# Sheet1.net
KiCad netlist of a schematic drawn in Altium Designer
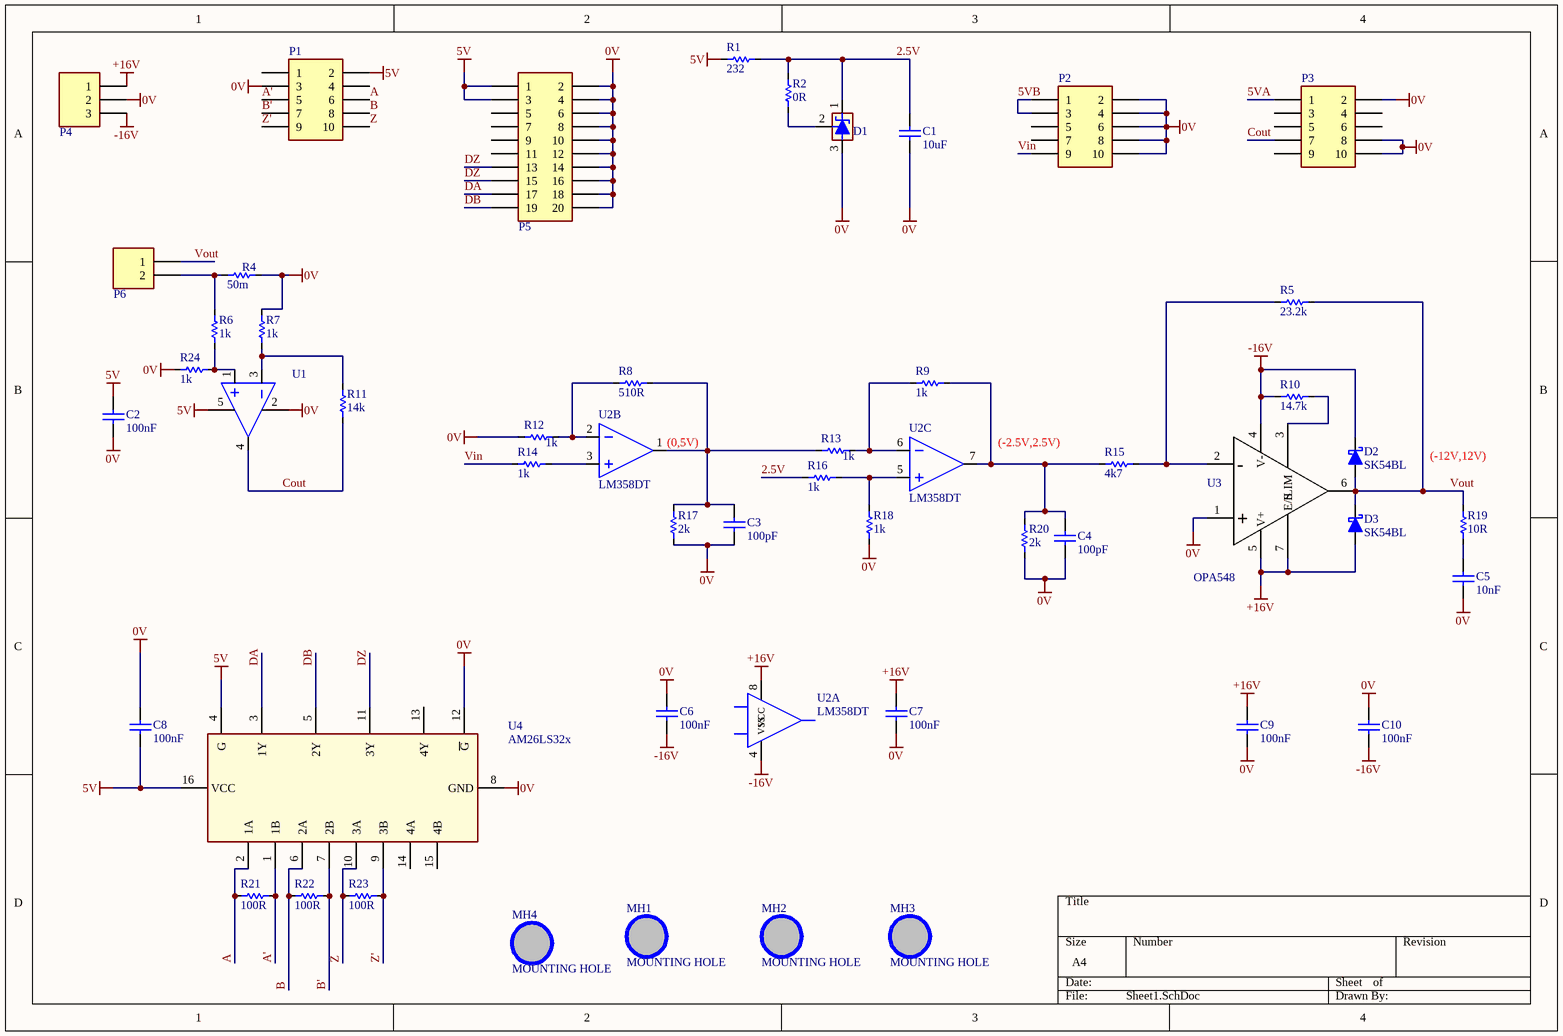
[diagram p0: Sheet1.SchDoc]

(export (version "E")
  (design (tool "Eeschema 10.0.6"))
  (components
    (comp (ref "C1")
      (value "10uF")
      (footprint "CC3216-1206L")
      (description "Capacitor")
      (libsource (lib "SchLibrary") (part "CAPACITOR NON-POL"))
    )
    (comp (ref "C2")
      (value "100nF")
      (footprint "CC3216-1206L")
      (description "Capacitor")
      (libsource (lib "SchLibrary") (part "CAPACITOR NON-POL"))
    )
    (comp (ref "C3")
      (value "100pF")
      (footprint "CC3216-1206L")
      (description "Capacitor")
      (libsource (lib "SchLibrary") (part "CAPACITOR NON-POL"))
    )
    (comp (ref "C4")
      (value "100pF")
      (footprint "CC3216-1206L")
      (description "Capacitor")
      (libsource (lib "SchLibrary") (part "CAPACITOR NON-POL"))
    )
    (comp (ref "C5")
      (value "10nF")
      (footprint "CC3216-1206L")
      (description "Capacitor")
      (libsource (lib "SchLibrary") (part "CAPACITOR NON-POL"))
    )
    (comp (ref "C6")
      (value "100nF")
      (footprint "CC3216-1206L")
      (description "Capacitor")
      (libsource (lib "SchLibrary") (part "CAPACITOR NON-POL"))
    )
    (comp (ref "C7")
      (value "100nF")
      (footprint "CC3216-1206L")
      (description "Capacitor")
      (libsource (lib "SchLibrary") (part "CAPACITOR NON-POL"))
    )
    (comp (ref "C8")
      (value "100nF")
      (footprint "CC3216-1206L")
      (description "Capacitor")
      (libsource (lib "SchLibrary") (part "CAPACITOR NON-POL"))
    )
    (comp (ref "C9")
      (value "100nF")
      (footprint "CC3216-1206L")
      (description "Capacitor")
      (libsource (lib "SchLibrary") (part "CAPACITOR NON-POL"))
    )
    (comp (ref "C10")
      (value "100nF")
      (footprint "CC3216-1206L")
      (description "Capacitor")
      (libsource (lib "SchLibrary") (part "CAPACITOR NON-POL"))
    )
    (comp (ref "D1")
      (value "TL431")
      (footprint "SOT95P230X110-3N")
      (description "REFERENCE DIODE PIN1:C, PIN2:REF, PIN3:A")
      (libsource (lib "SchLibrary") (part "TL431"))
    )
    (comp (ref "D2")
      (value "SK54BL")
      (footprint "PcbLibrary:SMB")
      (description "SINGLE SCHOTTKY DIODE\r\nCheck the suitability of the case with the pin number")
      (libsource (lib "SchLibrary") (part "DIODE SCHOTTKY"))
    )
    (comp (ref "D3")
      (value "SK54BL")
      (footprint "PcbLibrary:SMB")
      (description "SINGLE SCHOTTKY DIODE\r\nCheck the suitability of the case with the pin number")
      (libsource (lib "SchLibrary") (part "DIODE SCHOTTKY"))
    )
    (comp (ref "MH1")
      (value "MOUNTING HOLE")
      (footprint "PcbLibrary:MOUNTING HOLE ROUND NONPLATED 3MM PLASTIC")
      (libsource (lib "SchLibrary") (part "MOUNTING HOLE"))
    )
    (comp (ref "MH2")
      (value "MOUNTING HOLE")
      (footprint "PcbLibrary:MOUNTING HOLE ROUND NONPLATED 3MM PLASTIC")
      (libsource (lib "SchLibrary") (part "MOUNTING HOLE"))
    )
    (comp (ref "MH3")
      (value "MOUNTING HOLE")
      (footprint "PcbLibrary:MOUNTING HOLE ROUND NONPLATED 3MM PLASTIC")
      (libsource (lib "SchLibrary") (part "MOUNTING HOLE"))
    )
    (comp (ref "MH4")
      (value "MOUNTING HOLE")
      (footprint "PcbLibrary:MOUNTING HOLE ROUND NONPLATED 3MM PLASTIC")
      (libsource (lib "SchLibrary") (part "MOUNTING HOLE"))
    )
    (comp (ref "P1")
      (value "CONNECTOR, 2x5, 5P")
      (footprint "PcbLibrary:HDR_BOX_2X5_10P_2.54MM_180")
      (description "CONNECTOR, 2x5, 10P")
      (libsource (lib "SchLibrary") (part "CONNECTOR, 2x5, 10P"))
    )
    (comp (ref "P2")
      (value "CONNECTOR, 2x5, 5P")
      (footprint "PcbLibrary:HDR_FEMALE_2X5_10P_2.54MM_180")
      (description "CONNECTOR, 2x5, 10P")
      (libsource (lib "SchLibrary") (part "CONNECTOR, 2x5, 10P"))
    )
    (comp (ref "P3")
      (value "CONNECTOR, 2x5, 5P")
      (footprint "PcbLibrary:HDR_FEMALE_2X5_10P_2.54MM_180")
      (description "CONNECTOR, 2x5, 10P")
      (libsource (lib "SchLibrary") (part "CONNECTOR, 2x5, 10P"))
    )
    (comp (ref "P4")
      (value "CONNECTOR, 1x3, 3P")
      (footprint "PcbLibrary:2EDGR-5.08-03P")
      (libsource (lib "SchLibrary") (part "CONNECTOR, 1x3, 3P"))
    )
    (comp (ref "P5")
      (value "CONNECTOR, 2x10, 20P")
      (footprint "PcbLibrary:HDR_MALE_2X10_20P_2.54MM_180")
      (libsource (lib "SchLibrary") (part "CONNECTOR, 2x10, 20P"))
    )
    (comp (ref "P6")
      (value "CONNECTOR, 1x2, 2P")
      (footprint "PcbLibrary:DG128-5.0-02P-14")
      (libsource (lib "SchLibrary") (part "CONNECTOR, 1x2, 2P"))
    )
    (comp (ref "R1")
      (value "232")
      (footprint "CR3216-1206l")
      (description "Resistor")
      (libsource (lib "SchLibrary") (part "RESISTOR"))
    )
    (comp (ref "R2")
      (value "0R")
      (footprint "CR3216-1206l")
      (description "Resistor")
      (libsource (lib "SchLibrary") (part "RESISTOR"))
    )
    (comp (ref "R4")
      (value "50m")
      (footprint "CR3216-1206l")
      (description "Resistor")
      (libsource (lib "SchLibrary") (part "RESISTOR"))
    )
    (comp (ref "R5")
      (value "23.2k")
      (footprint "CR3216-1206l")
      (description "Resistor")
      (libsource (lib "SchLibrary") (part "RESISTOR"))
    )
    (comp (ref "R6")
      (value "1k")
      (footprint "CR3216-1206l")
      (description "Resistor")
      (libsource (lib "SchLibrary") (part "RESISTOR"))
    )
    (comp (ref "R7")
      (value "1k")
      (footprint "CR3216-1206l")
      (description "Resistor")
      (libsource (lib "SchLibrary") (part "RESISTOR"))
    )
    (comp (ref "R8")
      (value "510R")
      (footprint "CR3216-1206l")
      (description "Resistor")
      (libsource (lib "SchLibrary") (part "RESISTOR"))
    )
    (comp (ref "R9")
      (value "1k")
      (footprint "CR3216-1206l")
      (description "Resistor")
      (libsource (lib "SchLibrary") (part "RESISTOR"))
    )
    (comp (ref "R10")
      (value "14.7k")
      (footprint "CR3216-1206l")
      (description "Resistor")
      (libsource (lib "SchLibrary") (part "RESISTOR"))
    )
    (comp (ref "R11")
      (value "14k")
      (footprint "CR3216-1206l")
      (description "Resistor")
      (libsource (lib "SchLibrary") (part "RESISTOR"))
    )
    (comp (ref "R12")
      (value "1k")
      (footprint "CR3216-1206l")
      (description "Resistor")
      (libsource (lib "SchLibrary") (part "RESISTOR"))
    )
    (comp (ref "R13")
      (value "1k")
      (footprint "CR3216-1206l")
      (description "Resistor")
      (libsource (lib "SchLibrary") (part "RESISTOR"))
    )
    (comp (ref "R14")
      (value "1k")
      (footprint "CR3216-1206l")
      (description "Resistor")
      (libsource (lib "SchLibrary") (part "RESISTOR"))
    )
    (comp (ref "R15")
      (value "4k7")
      (footprint "CR3216-1206l")
      (description "Resistor")
      (libsource (lib "SchLibrary") (part "RESISTOR"))
    )
    (comp (ref "R16")
      (value "1k")
      (footprint "CR3216-1206l")
      (description "Resistor")
      (libsource (lib "SchLibrary") (part "RESISTOR"))
    )
    (comp (ref "R17")
      (value "2k")
      (footprint "CR3216-1206l")
      (description "Resistor")
      (libsource (lib "SchLibrary") (part "RESISTOR"))
    )
    (comp (ref "R18")
      (value "1k")
      (footprint "CR3216-1206l")
      (description "Resistor")
      (libsource (lib "SchLibrary") (part "RESISTOR"))
    )
    (comp (ref "R19")
      (value "10R")
      (footprint "CR3216-1206l")
      (description "Resistor")
      (libsource (lib "SchLibrary") (part "RESISTOR"))
    )
    (comp (ref "R20")
      (value "2k")
      (footprint "CR3216-1206l")
      (description "Resistor")
      (libsource (lib "SchLibrary") (part "RESISTOR"))
    )
    (comp (ref "R21")
      (value "100R")
      (footprint "CR3216-1206l")
      (description "Resistor")
      (libsource (lib "SchLibrary") (part "RESISTOR"))
    )
    (comp (ref "R22")
      (value "100R")
      (footprint "CR3216-1206l")
      (description "Resistor")
      (libsource (lib "SchLibrary") (part "RESISTOR"))
    )
    (comp (ref "R23")
      (value "100R")
      (footprint "CR3216-1206l")
      (description "Resistor")
      (libsource (lib "SchLibrary") (part "RESISTOR"))
    )
    (comp (ref "R24")
      (value "1k")
      (footprint "CR3216-1206l")
      (description "Resistor")
      (libsource (lib "SchLibrary") (part "RESISTOR"))
    )
    (comp (ref "U1")
      (value "LMV321")
      (footprint "LMV321IDBVTE4:SOT95P280X145-5N")
      (description "Single Opamp\r\nCheck the suitability of the case with the pin number")
      (libsource (lib "SchLibrary") (part "OPAMP1"))
    )
    (comp (ref "U2")
      (value "LM358DT")
      (footprint "SOIC127P600X175-8N")
      (description "Dual Opamp")
      (libsource (lib "SchLibrary") (part "OPAMP2"))
    )
    (comp (ref "U3")
      (value "OPA548")
      (footprint "TO127P1524X465-8N:TO127P1524X465-8N")
      (libsource (lib "SchLibrary") (part "OPA548"))
    )
    (comp (ref "U4")
      (value "AM26LS32x")
      (footprint "SOIC127P600X175-16N")
      (libsource (lib "SchLibrary") (part "AM26LS32x"))
    )
  )
  (nets
    (net (code "1") (name "+16V") (class "Default")
      (node (ref "C7") (pin "2") (pintype "passive"))
      (node (ref "C9") (pin "2") (pintype "passive"))
      (node (ref "D3") (pin "1") (pinfunction "1_1") (pintype "passive"))
      (node (ref "P4") (pin "1") (pinfunction "1_1") (pintype "passive"))
      (node (ref "U2") (pin "8") (pinfunction "VCC_8") (pintype "passive"))
      (node (ref "U3") (pin "5") (pinfunction "V+_5") (pintype "passive"))
      (node (ref "U3") (pin "7") (pinfunction "E/S_7") (pintype "passive"))
    )
    (net (code "2") (name "-16V") (class "Default")
      (node (ref "C10") (pin "1") (pintype "passive"))
      (node (ref "C6") (pin "1") (pintype "passive"))
      (node (ref "D2") (pin "2") (pinfunction "2_2") (pintype "passive"))
      (node (ref "P4") (pin "3") (pinfunction "3_3") (pintype "passive"))
      (node (ref "R10") (pin "2") (pinfunction "2_2") (pintype "passive"))
      (node (ref "U2") (pin "4") (pinfunction "VSS_4") (pintype "passive"))
      (node (ref "U3") (pin "4") (pinfunction "V-_4") (pintype "passive"))
    )
    (net (code "3") (name "/2.5V") (class "Default")
      (node (ref "C1") (pin "1") (pintype "passive"))
      (node (ref "D1") (pin "1") (pinfunction "C_1") (pintype "passive"))
      (node (ref "R1") (pin "1") (pinfunction "1_1") (pintype "passive"))
      (node (ref "R16") (pin "2") (pinfunction "2_2") (pintype "passive"))
      (node (ref "R2") (pin "2") (pinfunction "2_2") (pintype "passive"))
    )
    (net (code "4") (name "/5VA") (class "Default")
      (node (ref "P3") (pin "1") (pinfunction "1_1") (pintype "passive"))
    )
    (net (code "5") (name "/5VB") (class "Default")
      (node (ref "P2") (pin "1") (pinfunction "1_1") (pintype "passive"))
      (node (ref "P2") (pin "3") (pinfunction "3_3") (pintype "passive"))
    )
    (net (code "6") (name "/A") (class "Default")
      (node (ref "P1") (pin "6") (pinfunction "6_6") (pintype "passive"))
      (node (ref "R21") (pin "2") (pinfunction "2_2") (pintype "passive"))
      (node (ref "U4") (pin "2") (pinfunction "1A_2") (pintype "passive"))
    )
    (net (code "7") (name "/A'") (class "Default")
      (node (ref "P1") (pin "5") (pinfunction "5_5") (pintype "passive"))
      (node (ref "R21") (pin "1") (pinfunction "1_1") (pintype "passive"))
      (node (ref "U4") (pin "1") (pinfunction "1B_1") (pintype "passive"))
    )
    (net (code "8") (name "/B") (class "Default")
      (node (ref "P1") (pin "8") (pinfunction "8_8") (pintype "passive"))
      (node (ref "R22") (pin "2") (pinfunction "2_2") (pintype "passive"))
      (node (ref "U4") (pin "6") (pinfunction "2A_6") (pintype "passive"))
    )
    (net (code "9") (name "/B'") (class "Default")
      (node (ref "P1") (pin "7") (pinfunction "7_7") (pintype "passive"))
      (node (ref "R22") (pin "1") (pinfunction "1_1") (pintype "passive"))
      (node (ref "U4") (pin "7") (pinfunction "2B_7") (pintype "passive"))
    )
    (net (code "10") (name "/Cout") (class "Default")
      (node (ref "P3") (pin "7") (pinfunction "7_7") (pintype "passive"))
      (node (ref "R11") (pin "2") (pinfunction "2_2") (pintype "passive"))
      (node (ref "U1") (pin "4") (pinfunction "VSS_4") (pintype "passive"))
    )
    (net (code "11") (name "/DA") (class "Default")
      (node (ref "P5") (pin "17") (pinfunction "17_17") (pintype "passive"))
      (node (ref "U4") (pin "3") (pinfunction "1Y_3") (pintype "passive"))
    )
    (net (code "12") (name "/DB") (class "Default")
      (node (ref "P5") (pin "19") (pinfunction "19_19") (pintype "passive"))
      (node (ref "U4") (pin "5") (pinfunction "2Y_5") (pintype "passive"))
    )
    (net (code "13") (name "/DZ") (class "Default")
      (node (ref "P5") (pin "13") (pinfunction "13_13") (pintype "passive"))
      (node (ref "P5") (pin "15") (pinfunction "15_15") (pintype "passive"))
      (node (ref "U4") (pin "11") (pinfunction "3Y_11") (pintype "passive"))
    )
    (net (code "14") (name "/Vin") (class "Default")
      (node (ref "P2") (pin "9") (pinfunction "9_9") (pintype "passive"))
      (node (ref "R14") (pin "2") (pinfunction "2_2") (pintype "passive"))
    )
    (net (code "15") (name "/Vout") (class "Default")
      (node (ref "D2") (pin "1") (pinfunction "1_1") (pintype "passive"))
      (node (ref "D3") (pin "2") (pinfunction "2_2") (pintype "passive"))
      (node (ref "P6") (pin "1") (pinfunction "1_1") (pintype "passive"))
      (node (ref "R19") (pin "2") (pinfunction "2_2") (pintype "passive"))
      (node (ref "R5") (pin "1") (pinfunction "1_1") (pintype "passive"))
      (node (ref "U3") (pin "6") (pinfunction "Vo_6") (pintype "passive"))
    )
    (net (code "16") (name "/Z") (class "Default")
      (node (ref "P1") (pin "10") (pinfunction "10_10") (pintype "passive"))
      (node (ref "R23") (pin "2") (pinfunction "2_2") (pintype "passive"))
      (node (ref "U4") (pin "10") (pinfunction "3A_10") (pintype "passive"))
    )
    (net (code "17") (name "/Z'") (class "Default")
      (node (ref "P1") (pin "9") (pinfunction "9_9") (pintype "passive"))
      (node (ref "R23") (pin "1") (pinfunction "1_1") (pintype "passive"))
      (node (ref "U4") (pin "9") (pinfunction "3B_9") (pintype "passive"))
    )
    (net (code "18") (name "0V") (class "Default")
      (node (ref "C1") (pin "2") (pintype "passive"))
      (node (ref "C10") (pin "2") (pintype "passive"))
      (node (ref "C2") (pin "2") (pintype "passive"))
      (node (ref "C3") (pin "1") (pintype "passive"))
      (node (ref "C4") (pin "1") (pintype "passive"))
      (node (ref "C5") (pin "1") (pintype "passive"))
      (node (ref "C6") (pin "2") (pintype "passive"))
      (node (ref "C7") (pin "1") (pintype "passive"))
      (node (ref "C8") (pin "2") (pintype "passive"))
      (node (ref "C9") (pin "1") (pintype "passive"))
      (node (ref "D1") (pin "3") (pinfunction "A_3") (pintype "passive"))
      (node (ref "P1") (pin "3") (pinfunction "3_3") (pintype "passive"))
      (node (ref "P2") (pin "10") (pinfunction "10_10") (pintype "passive"))
      (node (ref "P2") (pin "2") (pinfunction "2_2") (pintype "passive"))
      (node (ref "P2") (pin "4") (pinfunction "4_4") (pintype "passive"))
      (node (ref "P2") (pin "6") (pinfunction "6_6") (pintype "passive"))
      (node (ref "P2") (pin "8") (pinfunction "8_8") (pintype "passive"))
      (node (ref "P3") (pin "10") (pinfunction "10_10") (pintype "passive"))
      (node (ref "P3") (pin "2") (pinfunction "2_2") (pintype "passive"))
      (node (ref "P3") (pin "8") (pinfunction "8_8") (pintype "passive"))
      (node (ref "P4") (pin "2") (pinfunction "2_2") (pintype "passive"))
      (node (ref "P5") (pin "10") (pinfunction "10_10") (pintype "passive"))
      (node (ref "P5") (pin "12") (pinfunction "12_12") (pintype "passive"))
      (node (ref "P5") (pin "14") (pinfunction "14_14") (pintype "passive"))
      (node (ref "P5") (pin "16") (pinfunction "16_16") (pintype "passive"))
      (node (ref "P5") (pin "18") (pinfunction "18_18") (pintype "passive"))
      (node (ref "P5") (pin "2") (pinfunction "2_2") (pintype "passive"))
      (node (ref "P5") (pin "20") (pinfunction "20_20") (pintype "passive"))
      (node (ref "P5") (pin "4") (pinfunction "4_4") (pintype "passive"))
      (node (ref "P5") (pin "6") (pinfunction "6_6") (pintype "passive"))
      (node (ref "P5") (pin "8") (pinfunction "8_8") (pintype "passive"))
      (node (ref "R12") (pin "2") (pinfunction "2_2") (pintype "passive"))
      (node (ref "R17") (pin "2") (pinfunction "2_2") (pintype "passive"))
      (node (ref "R18") (pin "2") (pinfunction "2_2") (pintype "passive"))
      (node (ref "R20") (pin "2") (pinfunction "2_2") (pintype "passive"))
      (node (ref "R24") (pin "1") (pinfunction "1_1") (pintype "passive"))
      (node (ref "R4") (pin "1") (pinfunction "1_1") (pintype "passive"))
      (node (ref "R7") (pin "1") (pinfunction "1_1") (pintype "passive"))
      (node (ref "U1") (pin "2") (pinfunction "2_2") (pintype "passive"))
      (node (ref "U3") (pin "1") (pinfunction "+_1") (pintype "passive"))
      (node (ref "U4") (pin "12") (pinfunction "~{G}_12") (pintype "passive"))
      (node (ref "U4") (pin "8") (pinfunction "GND_8") (pintype "passive"))
    )
    (net (code "19") (name "5V") (class "Default")
      (node (ref "C2") (pin "1") (pintype "passive"))
      (node (ref "C8") (pin "1") (pintype "passive"))
      (node (ref "P1") (pin "2") (pinfunction "2_2") (pintype "passive"))
      (node (ref "P5") (pin "1") (pinfunction "1_1") (pintype "passive"))
      (node (ref "P5") (pin "3") (pinfunction "3_3") (pintype "passive"))
      (node (ref "R1") (pin "2") (pinfunction "2_2") (pintype "passive"))
      (node (ref "U1") (pin "5") (pinfunction "VCC_5") (pintype "passive"))
      (node (ref "U4") (pin "16") (pinfunction "VCC_16") (pintype "passive"))
      (node (ref "U4") (pin "4") (pinfunction "G_4") (pintype "passive"))
    )
    (net (code "20") (name "Net-(C3-Pad2)") (class "Default")
      (node (ref "C3") (pin "2") (pintype "passive"))
      (node (ref "R13") (pin "2") (pinfunction "2_2") (pintype "passive"))
      (node (ref "R17") (pin "1") (pinfunction "1_1") (pintype "passive"))
      (node (ref "R8") (pin "1") (pinfunction "1_1") (pintype "passive"))
      (node (ref "U2") (pin "1") (pinfunction "1_1") (pintype "passive"))
    )
    (net (code "21") (name "Net-(C4-Pad2)") (class "Default")
      (node (ref "C4") (pin "2") (pintype "passive"))
      (node (ref "R15") (pin "2") (pinfunction "2_2") (pintype "passive"))
      (node (ref "R20") (pin "1") (pinfunction "1_1") (pintype "passive"))
      (node (ref "R9") (pin "1") (pinfunction "1_1") (pintype "passive"))
      (node (ref "U2") (pin "7") (pinfunction "7_7") (pintype "passive"))
    )
    (net (code "22") (name "Net-(C5-Pad2)") (class "Default")
      (node (ref "C5") (pin "2") (pintype "passive"))
      (node (ref "R19") (pin "1") (pinfunction "1_1") (pintype "passive"))
    )
    (net (code "23") (name "Net-(D1-REF)") (class "Default")
      (node (ref "D1") (pin "2") (pinfunction "REF_2") (pintype "passive"))
      (node (ref "R2") (pin "1") (pinfunction "1_1") (pintype "passive"))
    )
    (net (code "24") (name "Net-(P6-Pad2)") (class "Default")
      (node (ref "P6") (pin "2") (pinfunction "2_2") (pintype "passive"))
      (node (ref "R4") (pin "2") (pinfunction "2_2") (pintype "passive"))
      (node (ref "R6") (pin "1") (pinfunction "1_1") (pintype "passive"))
    )
    (net (code "25") (name "Net-(R11-Pad1)") (class "Default")
      (node (ref "R11") (pin "1") (pinfunction "1_1") (pintype "passive"))
      (node (ref "R7") (pin "2") (pinfunction "2_2") (pintype "passive"))
      (node (ref "U1") (pin "3") (pinfunction "3_3") (pintype "passive"))
    )
    (net (code "26") (name "Net-(R12-Pad1)") (class "Default")
      (node (ref "R12") (pin "1") (pinfunction "1_1") (pintype "passive"))
      (node (ref "R8") (pin "2") (pinfunction "2_2") (pintype "passive"))
      (node (ref "U2") (pin "2") (pinfunction "2_2") (pintype "passive"))
    )
    (net (code "27") (name "Net-(R13-Pad1)") (class "Default")
      (node (ref "R13") (pin "1") (pinfunction "1_1") (pintype "passive"))
      (node (ref "R9") (pin "2") (pinfunction "2_2") (pintype "passive"))
      (node (ref "U2") (pin "6") (pinfunction "6_6") (pintype "passive"))
    )
    (net (code "28") (name "Net-(R14-Pad1)") (class "Default")
      (node (ref "R14") (pin "1") (pinfunction "1_1") (pintype "passive"))
      (node (ref "U2") (pin "3") (pinfunction "3_3") (pintype "passive"))
    )
    (net (code "29") (name "Net-(R16-Pad1)") (class "Default")
      (node (ref "R16") (pin "1") (pinfunction "1_1") (pintype "passive"))
      (node (ref "R18") (pin "1") (pinfunction "1_1") (pintype "passive"))
      (node (ref "U2") (pin "5") (pinfunction "5_5") (pintype "passive"))
    )
    (net (code "30") (name "Net-(R24-Pad2)") (class "Default")
      (node (ref "R24") (pin "2") (pinfunction "2_2") (pintype "passive"))
      (node (ref "R6") (pin "2") (pinfunction "2_2") (pintype "passive"))
      (node (ref "U1") (pin "1") (pinfunction "1_1") (pintype "passive"))
    )
    (net (code "31") (name "Net-(U3--)") (class "Default")
      (node (ref "R15") (pin "1") (pinfunction "1_1") (pintype "passive"))
      (node (ref "R5") (pin "2") (pinfunction "2_2") (pintype "passive"))
      (node (ref "U3") (pin "2") (pinfunction "-_2") (pintype "passive"))
    )
    (net (code "32") (name "Net-(U3-ILIM)") (class "Default")
      (node (ref "R10") (pin "1") (pinfunction "1_1") (pintype "passive"))
      (node (ref "U3") (pin "3") (pinfunction "ILIM_3") (pintype "passive"))
    )
    (net (code "33") (name "unconnected-(P1-Pad1)") (class "Default")
      (node (ref "P1") (pin "1") (pinfunction "1_1") (pintype "passive"))
    )
    (net (code "34") (name "unconnected-(P1-Pad4)") (class "Default")
      (node (ref "P1") (pin "4") (pinfunction "4_4") (pintype "passive"))
    )
    (net (code "35") (name "unconnected-(P2-Pad5)") (class "Default")
      (node (ref "P2") (pin "5") (pinfunction "5_5") (pintype "passive"))
    )
    (net (code "36") (name "unconnected-(P2-Pad7)") (class "Default")
      (node (ref "P2") (pin "7") (pinfunction "7_7") (pintype "passive"))
    )
    (net (code "37") (name "unconnected-(P3-Pad3)") (class "Default")
      (node (ref "P3") (pin "3") (pinfunction "3_3") (pintype "passive"))
    )
    (net (code "38") (name "unconnected-(P3-Pad4)") (class "Default")
      (node (ref "P3") (pin "4") (pinfunction "4_4") (pintype "passive"))
    )
    (net (code "39") (name "unconnected-(P3-Pad5)") (class "Default")
      (node (ref "P3") (pin "5") (pinfunction "5_5") (pintype "passive"))
    )
    (net (code "40") (name "unconnected-(P3-Pad6)") (class "Default")
      (node (ref "P3") (pin "6") (pinfunction "6_6") (pintype "passive"))
    )
    (net (code "41") (name "unconnected-(P3-Pad9)") (class "Default")
      (node (ref "P3") (pin "9") (pinfunction "9_9") (pintype "passive"))
    )
    (net (code "42") (name "unconnected-(P5-Pad5)") (class "Default")
      (node (ref "P5") (pin "5") (pinfunction "5_5") (pintype "passive"))
    )
    (net (code "43") (name "unconnected-(P5-Pad7)") (class "Default")
      (node (ref "P5") (pin "7") (pinfunction "7_7") (pintype "passive"))
    )
    (net (code "44") (name "unconnected-(P5-Pad9)") (class "Default")
      (node (ref "P5") (pin "9") (pinfunction "9_9") (pintype "passive"))
    )
    (net (code "45") (name "unconnected-(P5-Pad11)") (class "Default")
      (node (ref "P5") (pin "11") (pinfunction "11_11") (pintype "passive"))
    )
    (net (code "46") (name "unconnected-(U4-4A-Pad14)") (class "Default")
      (node (ref "U4") (pin "14") (pinfunction "4A_14") (pintype "passive"))
    )
    (net (code "47") (name "unconnected-(U4-4B-Pad15)") (class "Default")
      (node (ref "U4") (pin "15") (pinfunction "4B_15") (pintype "passive"))
    )
    (net (code "48") (name "unconnected-(U4-4Y-Pad13)") (class "Default")
      (node (ref "U4") (pin "13") (pinfunction "4Y_13") (pintype "passive"))
    )
  )
)
